# FOX_HTOL_test_2_0.net
KiCad netlist of a schematic drawn in EasyEDA Pro
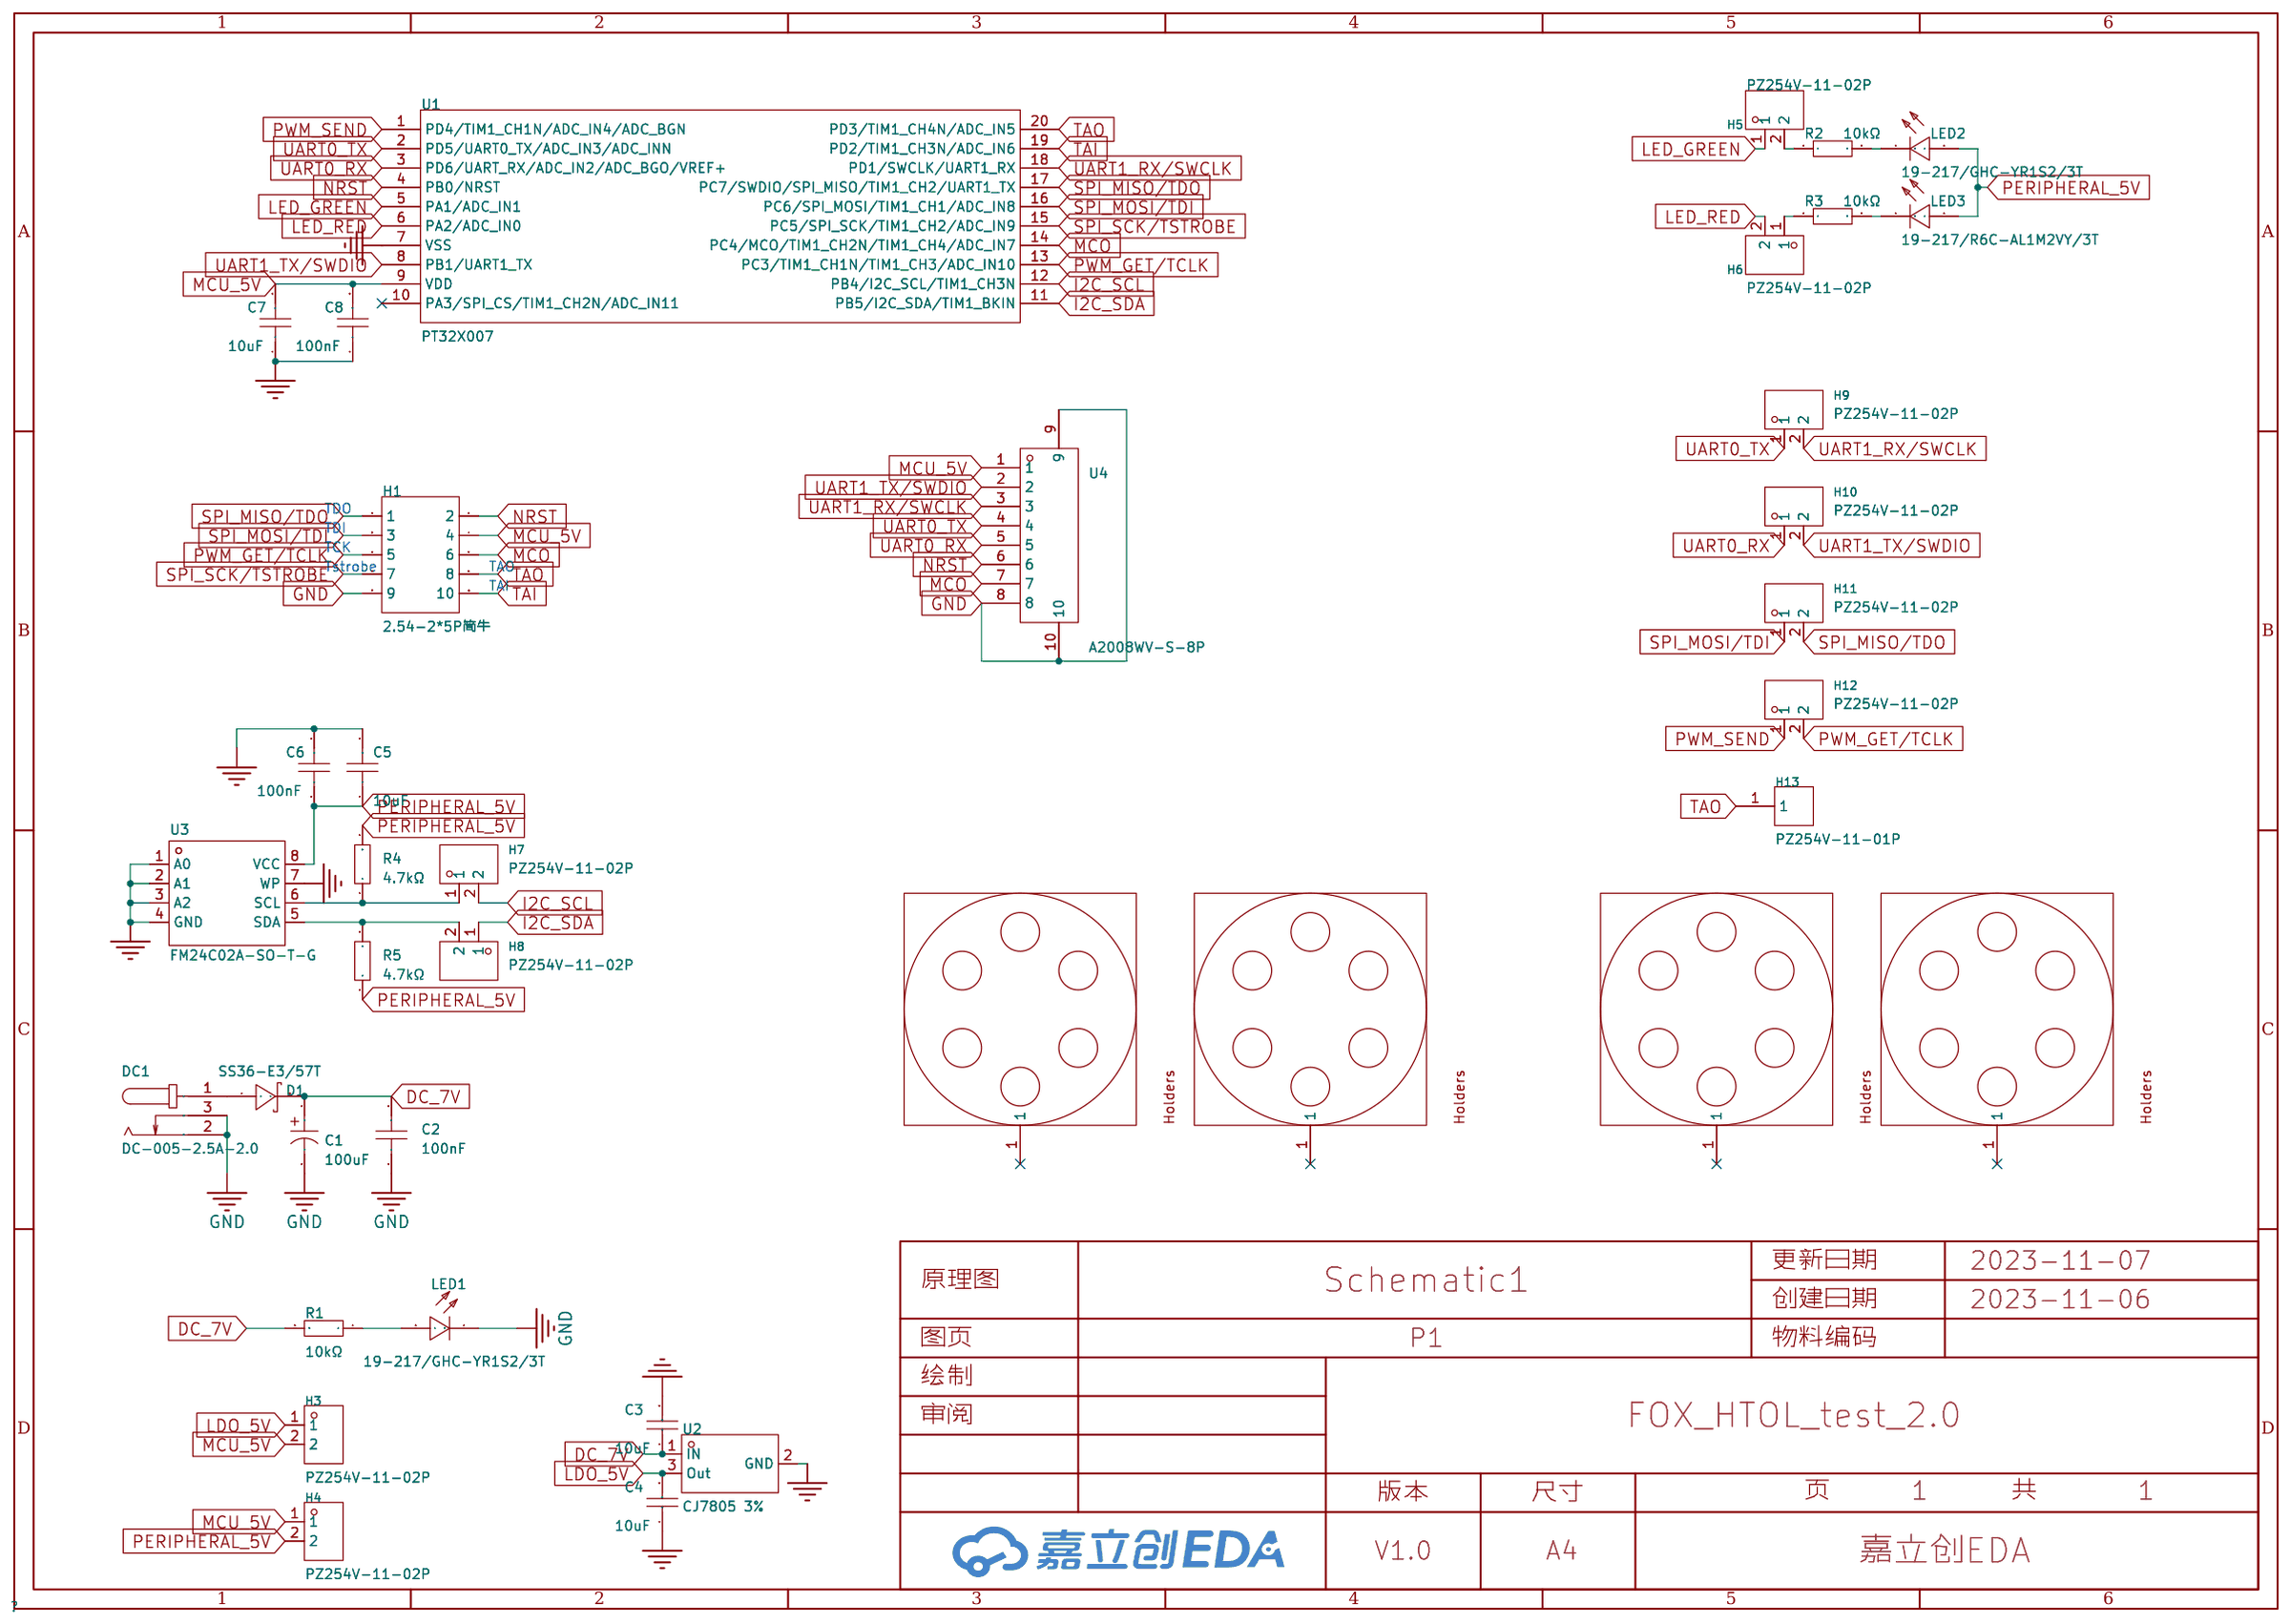
[diagram p0: schematic sheet]

(export (version "E")
  (design (tool "Eeschema 10.0.6"))
  (components
    (comp (ref "C1")
      (value "100uF")
      (footprint "easyedapro:CAP-SMD_BD6.3-L6.6-W6.6-LS7.6-FD-1")
      (description "容值:100uF;额定电压:35V;电容体直径:-;电容体长度:-;纹波电流:-;等效串联电阻:-;工作寿命:-;")
      (fields
        (field (name "Manufacturer Part") "RVE100UF35V67RV0072")
        (field (name "Manufacturer") "KNSCHA(科尼盛)")
      )
      (libsource (lib "easyedapro") (part "RVE100UF35V67RV0072"))
    )
    (comp (ref "C2")
      (value "100nF")
      (footprint "easyedapro:C0603")
      (description "容值:100nF;精度:±10%;额定电压:50V;材质(温度系数):X7R;")
      (fields
        (field (name "Manufacturer Part") "CL10B104KB8NNNC")
        (field (name "Manufacturer") "SAMSUNG(三星)")
      )
      (libsource (lib "easyedapro") (part "CL10B104KB8NNNC"))
    )
    (comp (ref "C3")
      (value "10uF")
      (footprint "easyedapro:C1206")
      (description "容值:10uF;精度:±10%;额定电压:50V;材质(温度系数):X5R;")
      (fields
        (field (name "Manufacturer Part") "CL31A106KBHNNNE")
        (field (name "Manufacturer") "SAMSUNG(三星)")
      )
      (libsource (lib "easyedapro") (part "CL31A106KBHNNNE"))
    )
    (comp (ref "C4")
      (value "10uF")
      (footprint "easyedapro:C1206")
      (description "容值:10uF;精度:±10%;额定电压:50V;材质(温度系数):X5R;")
      (fields
        (field (name "Manufacturer Part") "CL31A106KBHNNNE")
        (field (name "Manufacturer") "SAMSUNG(三星)")
      )
      (libsource (lib "easyedapro") (part "CL31A106KBHNNNE"))
    )
    (comp (ref "C5")
      (value "10uF")
      (footprint "easyedapro:C0603")
      (description "容值:10uF;精度:±20%;额定电压:25V;材质(温度系数):X5R;")
      (fields
        (field (name "Manufacturer Part") "CL10A106MA8NRNC")
        (field (name "Manufacturer") "SAMSUNG(三星)")
      )
      (libsource (lib "easyedapro") (part "CL10A106MA8NRNC"))
    )
    (comp (ref "C6")
      (value "100nF")
      (footprint "easyedapro:C0603")
      (description "容值:100nF;精度:±10%;额定电压:50V;材质(温度系数):X7R;")
      (fields
        (field (name "Manufacturer Part") "CC0603KRX7R9BB104")
        (field (name "Manufacturer") "YAGEO(国巨)")
      )
      (libsource (lib "easyedapro") (part "CC0603KRX7R9BB104"))
    )
    (comp (ref "C7")
      (value "10uF")
      (footprint "easyedapro:C0603")
      (description "容值:10uF;精度:±20%;额定电压:25V;材质(温度系数):X5R;")
      (fields
        (field (name "Manufacturer Part") "CL10A106MA8NRNC")
        (field (name "Manufacturer") "SAMSUNG(三星)")
      )
      (libsource (lib "easyedapro") (part "CL10A106MA8NRNC"))
    )
    (comp (ref "C8")
      (value "100nF")
      (footprint "easyedapro:C0603")
      (description "容值:100nF;精度:±10%;额定电压:50V;材质(温度系数):X7R;")
      (fields
        (field (name "Manufacturer Part") "CC0603KRX7R9BB104")
        (field (name "Manufacturer") "YAGEO(国巨)")
      )
      (libsource (lib "easyedapro") (part "CC0603KRX7R9BB104"))
    )
    (comp (ref "D1")
      (value "SS36-E3/57T")
      (footprint "easyedapro:SMC_L7.1-W6.2-LS8.1-R-RD")
      (description "直流反向耐压（Vr）:60V;平均整流电流（Io）:3A;正向压降（Vf）:750mV @ 3A;")
      (fields (field (name "Manufacturer") "VISHAY(威世)"))
      (libsource (lib "easyedapro") (part "SS36-E3/57T"))
    )
    (comp (ref "DC1")
      (value "DC-005-2.5A-2.0")
      (footprint "easyedapro:CONN-TH_DC-005-2.5A-2.0")
      (fields (field (name "Manufacturer") "XKB Connectivity(中国星坤)"))
      (libsource (lib "easyedapro") (part "DC-005-2.5A-2.0"))
    )
    (comp (ref "H1")
      (value "2.54-2*5P简牛")
      (footprint "easyedapro:IDC-TH_10P-P2.54_C5665")
      (description "连接器类型:简牛座;每排PIN数:5;排数:2;间距:2.54mm;行距:2.54mm;封装形式:直插;触头材质:-;触头镀层:-;")
      (fields (field (name "Manufacturer") "BOOMELE(博穆精密)"))
      (libsource (lib "easyedapro") (part "HDR-IDC-2.54-2X5P"))
    )
    (comp (ref "H3")
      (value "PZ254V-11-02P")
      (footprint "easyedapro:HDR-TH_2P-P2.54-V-M")
      (fields (field (name "Manufacturer") "XFCN(兴飞)"))
      (libsource (lib "easyedapro") (part "PZ254V-11-02P"))
    )
    (comp (ref "H4")
      (value "PZ254V-11-02P")
      (footprint "easyedapro:HDR-TH_2P-P2.54-V-M")
      (fields (field (name "Manufacturer") "XFCN(兴飞)"))
      (libsource (lib "easyedapro") (part "PZ254V-11-02P"))
    )
    (comp (ref "H5")
      (value "PZ254V-11-02P")
      (footprint "easyedapro:HDR-TH_2P-P2.54-V-M")
      (fields (field (name "Manufacturer") "XFCN(兴飞)"))
      (libsource (lib "easyedapro") (part "PZ254V-11-02P"))
    )
    (comp (ref "H6")
      (value "PZ254V-11-02P")
      (footprint "easyedapro:HDR-TH_2P-P2.54-V-M")
      (fields (field (name "Manufacturer") "XFCN(兴飞)"))
      (libsource (lib "easyedapro") (part "PZ254V-11-02P"))
    )
    (comp (ref "H7")
      (value "PZ254V-11-02P")
      (footprint "easyedapro:HDR-TH_2P-P2.54-V-M")
      (fields (field (name "Manufacturer") "XFCN(兴飞)"))
      (libsource (lib "easyedapro") (part "PZ254V-11-02P"))
    )
    (comp (ref "H8")
      (value "PZ254V-11-02P")
      (footprint "easyedapro:HDR-TH_2P-P2.54-V-M")
      (fields (field (name "Manufacturer") "XFCN(兴飞)"))
      (libsource (lib "easyedapro") (part "PZ254V-11-02P"))
    )
    (comp (ref "H9")
      (value "PZ254V-11-02P")
      (footprint "easyedapro:HDR-TH_2P-P2.54-V-M")
      (fields (field (name "Manufacturer") "XFCN(兴飞)"))
      (libsource (lib "easyedapro") (part "PZ254V-11-02P"))
    )
    (comp (ref "H10")
      (value "PZ254V-11-02P")
      (footprint "easyedapro:HDR-TH_2P-P2.54-V-M")
      (fields (field (name "Manufacturer") "XFCN(兴飞)"))
      (libsource (lib "easyedapro") (part "PZ254V-11-02P"))
    )
    (comp (ref "H11")
      (value "PZ254V-11-02P")
      (footprint "easyedapro:HDR-TH_2P-P2.54-V-M")
      (fields (field (name "Manufacturer") "XFCN(兴飞)"))
      (libsource (lib "easyedapro") (part "PZ254V-11-02P"))
    )
    (comp (ref "H12")
      (value "PZ254V-11-02P")
      (footprint "easyedapro:HDR-TH_2P-P2.54-V-M")
      (fields (field (name "Manufacturer") "XFCN(兴飞)"))
      (libsource (lib "easyedapro") (part "PZ254V-11-02P"))
    )
    (comp (ref "H13")
      (value "PZ254V-11-01P")
      (footprint "easyedapro:HDR-TH_1P-P2.54-V-M")
      (fields (field (name "Manufacturer") "XFCN(兴飞)"))
      (libsource (lib "easyedapro") (part "PZ254V-11-01P"))
    )
    (comp (ref "J2")
      (value "~")
      (footprint "easyedapro:DEMO板安装孔")
      (libsource (lib "easyedapro") (part "螺孔_3.1X6MM"))
    )
    (comp (ref "J3")
      (value "~")
      (footprint "easyedapro:DEMO板安装孔")
      (libsource (lib "easyedapro") (part "螺孔_3.1X6MM"))
    )
    (comp (ref "J4")
      (value "~")
      (footprint "easyedapro:DEMO板安装孔")
      (libsource (lib "easyedapro") (part "螺孔_3.1X6MM"))
    )
    (comp (ref "J5")
      (value "~")
      (footprint "easyedapro:DEMO板安装孔")
      (libsource (lib "easyedapro") (part "螺孔_3.1X6MM"))
    )
    (comp (ref "LED1")
      (value "19-217/GHC-YR1S2/3T")
      (footprint "easyedapro:LED0603-RD")
      (fields (field (name "Manufacturer") "EVERLIGHT(亿光)"))
      (libsource (lib "easyedapro") (part "19-217/GHC-YR1S2/3T"))
    )
    (comp (ref "LED2")
      (value "19-217/GHC-YR1S2/3T")
      (footprint "easyedapro:LED0603-RD")
      (fields (field (name "Manufacturer") "EVERLIGHT(亿光)"))
      (libsource (lib "easyedapro") (part "19-217/GHC-YR1S2/3T"))
    )
    (comp (ref "LED3")
      (value "19-217/R6C-AL1M2VY/3T")
      (footprint "easyedapro:LED0603-RD")
      (description "发光颜色:红灯;二极管配置:-;透镜颜色:无色透明;主波长:617.5nm;色温:-;功率:60mW;发光角度:120°;安装方式:-;工作温度:-40°C~+85°C;")
      (fields (field (name "Manufacturer") "EVERLIGHT(亿光)"))
      (libsource (lib "easyedapro") (part "19-217/R6C-AL1M2VY/3T"))
    )
    (comp (ref "R1")
      (value "10kΩ")
      (footprint "easyedapro:R0603")
      (description "电阻类型:厚膜电阻;阻值:10kΩ;精度:±1%;功率:100mW;温度系数:±100ppm/℃;最大工作电压:75V;工作温度范围:-55℃~+155℃;")
      (fields
        (field (name "Manufacturer Part") "0603WAF1002T5E")
        (field (name "Manufacturer") "UNI-ROYAL(厚声)")
      )
      (libsource (lib "easyedapro") (part "0603WAF1002T5E"))
    )
    (comp (ref "R2")
      (value "10kΩ")
      (footprint "easyedapro:R0603")
      (description "电阻类型:厚膜电阻;阻值:10kΩ;精度:±1%;功率:100mW;")
      (fields
        (field (name "Manufacturer Part") "0603WAF1002T5E")
        (field (name "Manufacturer") "UNI-ROYAL(厚声)")
      )
      (libsource (lib "easyedapro") (part "0603WAF1002T5E"))
    )
    (comp (ref "R3")
      (value "10kΩ")
      (footprint "easyedapro:R0603")
      (description "电阻类型:厚膜电阻;阻值:10kΩ;精度:±1%;功率:100mW;")
      (fields
        (field (name "Manufacturer Part") "0603WAF1002T5E")
        (field (name "Manufacturer") "UNI-ROYAL(厚声)")
      )
      (libsource (lib "easyedapro") (part "0603WAF1002T5E"))
    )
    (comp (ref "R4")
      (value "4.7kΩ")
      (footprint "easyedapro:R0603")
      (description "电阻类型:厚膜电阻;阻值:4.7kΩ;精度:±1%;功率:100mW;温度系数:±100ppm/°C;")
      (fields
        (field (name "Manufacturer Part") "0603WAF4701T5E")
        (field (name "Manufacturer") "UNI-ROYAL(厚声)")
      )
      (libsource (lib "easyedapro") (part "0603WAF4701T5E"))
    )
    (comp (ref "R5")
      (value "4.7kΩ")
      (footprint "easyedapro:R0603")
      (description "电阻类型:厚膜电阻;阻值:4.7kΩ;精度:±1%;功率:100mW;温度系数:±100ppm/°C;")
      (fields
        (field (name "Manufacturer Part") "0603WAF4701T5E")
        (field (name "Manufacturer") "UNI-ROYAL(厚声)")
      )
      (libsource (lib "easyedapro") (part "0603WAF4701T5E"))
    )
    (comp (ref "U1")
      (value "PT32X007")
      (footprint "easyedapro:TSSOP-20_L6.5-W4.4-P0.65-LS6.4-BL")
      (libsource (lib "easyedapro") (part "PT32X007"))
    )
    (comp (ref "U2")
      (value "CJ7805 3%")
      (footprint "easyedapro:TO-252-2_L6.6-W6.1-P4.58-LS10.1-BR-CW")
      (description "输出类型:固定;输出极性:正;最大输入电压:35V;输出电压:5V;输出电流:1.5A;")
      (fields (field (name "Manufacturer") "CJ(江苏长电/长晶)"))
      (libsource (lib "easyedapro") (part "CJ7805 3%"))
    )
    (comp (ref "U3")
      (value "FM24C02A-SO-T-G")
      (footprint "easyedapro:SOP-8_L5.0-W4.0-P1.27-LS6.2-BL")
      (description "2-Kbit(256 x 8bit)，I2C接口，工作电压：1.7V to 5.5V")
      (fields (field (name "Manufacturer") "FM(复旦微)"))
      (libsource (lib "easyedapro") (part "FM24C02A-SO-TR"))
    )
    (comp (ref "U4")
      (value "A2008WV-S-8P")
      (footprint "easyedapro:CONN-SMD_A2008WV-S-8P")
      (description "参考系列:PH;间距:2mm;插针结构:1x8P;排数:1;每排PIN数:8;行距:-;安装方式:-;触头材质:黄铜;")
      (fields (field (name "Manufacturer") "CJT(长江连接器)"))
      (libsource (lib "easyedapro") (part "A2008WV-S-8P"))
    )
  )
  (nets
    (net (code "1") (name "DC_7V") (class "Default")
      (node (ref "C1") (pin "1") (pinfunction "1_1") (pintype "input"))
      (node (ref "C2") (pin "2") (pinfunction "2_2") (pintype "input"))
      (node (ref "C3") (pin "1") (pinfunction "1_1") (pintype "input"))
      (node (ref "D1") (pin "2") (pinfunction "K_2") (pintype "input"))
      (node (ref "R1") (pin "2") (pinfunction "2_2") (pintype "input"))
      (node (ref "U2") (pin "1") (pinfunction "IN_1") (pintype "input"))
    )
    (net (code "2") (name "GND") (class "Default")
      (node (ref "C1") (pin "2") (pinfunction "2_2") (pintype "input"))
      (node (ref "C2") (pin "1") (pinfunction "1_1") (pintype "input"))
      (node (ref "C3") (pin "2") (pinfunction "2_2") (pintype "input"))
      (node (ref "C4") (pin "1") (pinfunction "1_1") (pintype "input"))
      (node (ref "C5") (pin "2") (pinfunction "2_2") (pintype "input"))
      (node (ref "C6") (pin "2") (pinfunction "2_2") (pintype "input"))
      (node (ref "C7") (pin "1") (pinfunction "1_1") (pintype "input"))
      (node (ref "C8") (pin "1") (pinfunction "1_1") (pintype "input"))
      (node (ref "DC1") (pin "2") (pinfunction "2_2") (pintype "input"))
      (node (ref "DC1") (pin "3") (pinfunction "3_3") (pintype "input"))
      (node (ref "H1") (pin "9") (pinfunction "9_9") (pintype "input"))
      (node (ref "LED1") (pin "1") (pinfunction "C_1") (pintype "input"))
      (node (ref "U1") (pin "7") (pinfunction "VSS_7") (pintype "input"))
      (node (ref "U2") (pin "2") (pinfunction "GND_2") (pintype "input"))
      (node (ref "U3") (pin "1") (pinfunction "A0_1") (pintype "unspecified"))
      (node (ref "U3") (pin "2") (pinfunction "A1_2") (pintype "unspecified"))
      (node (ref "U3") (pin "3") (pinfunction "A2_3") (pintype "unspecified"))
      (node (ref "U3") (pin "4") (pinfunction "GND_4") (pintype "unspecified"))
      (node (ref "U3") (pin "7") (pinfunction "WP_7") (pintype "unspecified"))
      (node (ref "U4") (pin "10") (pinfunction "10_10") (pintype "input"))
      (node (ref "U4") (pin "8") (pinfunction "8_8") (pintype "input"))
      (node (ref "U4") (pin "9") (pinfunction "9_9") (pintype "input"))
    )
    (net (code "3") (name "I2C_SCL") (class "Default")
      (node (ref "H7") (pin "2") (pinfunction "2_2") (pintype "input"))
      (node (ref "U1") (pin "12") (pinfunction "PB4/I2C_SCL/TIM1_CH3N_12") (pintype "input"))
    )
    (net (code "4") (name "I2C_SDA") (class "Default")
      (node (ref "H8") (pin "1") (pinfunction "1_1") (pintype "input"))
      (node (ref "U1") (pin "11") (pinfunction "PB5/I2C_SDA/TIM1_BKIN_11") (pintype "input"))
    )
    (net (code "5") (name "LDO_5V") (class "Default")
      (node (ref "C4") (pin "2") (pinfunction "2_2") (pintype "input"))
      (node (ref "H3") (pin "1") (pinfunction "1_1") (pintype "input"))
      (node (ref "U2") (pin "3") (pinfunction "Out_3") (pintype "input"))
    )
    (net (code "6") (name "LED_GREEN") (class "Default")
      (node (ref "H5") (pin "1") (pinfunction "1_1") (pintype "input"))
      (node (ref "U1") (pin "5") (pinfunction "PA1/ADC_IN1_5") (pintype "input"))
    )
    (net (code "7") (name "LED_RED") (class "Default")
      (node (ref "H6") (pin "2") (pinfunction "2_2") (pintype "input"))
      (node (ref "U1") (pin "6") (pinfunction "PA2/ADC_IN0_6") (pintype "input"))
    )
    (net (code "8") (name "MCO") (class "Default")
      (node (ref "H1") (pin "6") (pinfunction "6_6") (pintype "input"))
      (node (ref "U1") (pin "14") (pinfunction "PC4/MCO/TIM1_CH2N/TIM1_CH4/ADC_IN7_14") (pintype "input"))
      (node (ref "U4") (pin "7") (pinfunction "7_7") (pintype "input"))
    )
    (net (code "9") (name "MCU_5V") (class "Default")
      (node (ref "C7") (pin "2") (pinfunction "2_2") (pintype "input"))
      (node (ref "C8") (pin "2") (pinfunction "2_2") (pintype "input"))
      (node (ref "H1") (pin "4") (pinfunction "4_4") (pintype "input"))
      (node (ref "H3") (pin "2") (pinfunction "2_2") (pintype "input"))
      (node (ref "H4") (pin "1") (pinfunction "1_1") (pintype "input"))
      (node (ref "U1") (pin "9") (pinfunction "VDD_9") (pintype "input"))
      (node (ref "U4") (pin "1") (pinfunction "1_1") (pintype "input"))
    )
    (net (code "10") (name "NRST") (class "Default")
      (node (ref "H1") (pin "2") (pinfunction "2_2") (pintype "input"))
      (node (ref "U1") (pin "4") (pinfunction "PB0/NRST_4") (pintype "input"))
      (node (ref "U4") (pin "6") (pinfunction "6_6") (pintype "input"))
    )
    (net (code "11") (name "Net-(D1-A)") (class "Default")
      (node (ref "D1") (pin "1") (pinfunction "A_1") (pintype "input"))
      (node (ref "DC1") (pin "1") (pinfunction "1_1") (pintype "input"))
    )
    (net (code "12") (name "Net-(H5-Pad2)") (class "Default")
      (node (ref "H5") (pin "2") (pinfunction "2_2") (pintype "input"))
      (node (ref "R2") (pin "1") (pinfunction "1_1") (pintype "input"))
    )
    (net (code "13") (name "Net-(H6-Pad1)") (class "Default")
      (node (ref "H6") (pin "1") (pinfunction "1_1") (pintype "input"))
      (node (ref "R3") (pin "1") (pinfunction "1_1") (pintype "input"))
    )
    (net (code "14") (name "Net-(LED1-A)") (class "Default")
      (node (ref "LED1") (pin "2") (pinfunction "A_2") (pintype "input"))
      (node (ref "R1") (pin "1") (pinfunction "1_1") (pintype "input"))
    )
    (net (code "15") (name "Net-(LED2-C)") (class "Default")
      (node (ref "LED2") (pin "1") (pinfunction "C_1") (pintype "input"))
      (node (ref "R2") (pin "2") (pinfunction "2_2") (pintype "input"))
    )
    (net (code "16") (name "Net-(LED3-C)") (class "Default")
      (node (ref "LED3") (pin "1") (pinfunction "C_1") (pintype "input"))
      (node (ref "R3") (pin "2") (pinfunction "2_2") (pintype "input"))
    )
    (net (code "17") (name "Net-(U3-SCL)") (class "Default")
      (node (ref "H7") (pin "1") (pinfunction "1_1") (pintype "input"))
      (node (ref "R4") (pin "1") (pinfunction "1_1") (pintype "input"))
      (node (ref "U3") (pin "6") (pinfunction "SCL_6") (pintype "unspecified"))
    )
    (net (code "18") (name "Net-(U3-SDA)") (class "Default")
      (node (ref "H8") (pin "2") (pinfunction "2_2") (pintype "input"))
      (node (ref "R5") (pin "2") (pinfunction "2_2") (pintype "input"))
      (node (ref "U3") (pin "5") (pinfunction "SDA_5") (pintype "unspecified"))
    )
    (net (code "19") (name "PERIPHERAL_5V") (class "Default")
      (node (ref "C5") (pin "1") (pinfunction "1_1") (pintype "input"))
      (node (ref "C6") (pin "1") (pinfunction "1_1") (pintype "input"))
      (node (ref "H4") (pin "2") (pinfunction "2_2") (pintype "input"))
      (node (ref "LED2") (pin "2") (pinfunction "A_2") (pintype "input"))
      (node (ref "LED3") (pin "2") (pinfunction "A_2") (pintype "input"))
      (node (ref "R4") (pin "2") (pinfunction "2_2") (pintype "input"))
      (node (ref "R5") (pin "1") (pinfunction "1_1") (pintype "input"))
      (node (ref "U3") (pin "8") (pinfunction "VCC_8") (pintype "unspecified"))
    )
    (net (code "20") (name "PWM_GET{slash}TCLK") (class "Default")
      (node (ref "H1") (pin "5") (pinfunction "5_5") (pintype "input"))
      (node (ref "H12") (pin "2") (pinfunction "2_2") (pintype "input"))
      (node (ref "U1") (pin "13") (pinfunction "PC3/TIM1_CH1N/TIM1_CH3/ADC_IN10_13") (pintype "input"))
    )
    (net (code "21") (name "PWM_SEND") (class "Default")
      (node (ref "H12") (pin "1") (pinfunction "1_1") (pintype "input"))
      (node (ref "U1") (pin "1") (pinfunction "PD4/TIM1_CH1N/ADC_IN4/ADC_BGN_1") (pintype "input"))
    )
    (net (code "22") (name "SPI_MISO{slash}TDO") (class "Default")
      (node (ref "H1") (pin "1") (pinfunction "1_1") (pintype "input"))
      (node (ref "H11") (pin "2") (pinfunction "2_2") (pintype "input"))
      (node (ref "U1") (pin "17") (pinfunction "PC7/SWDIO/SPI_MISO/TIM1_CH2/UART1_TX_17") (pintype "input"))
    )
    (net (code "23") (name "SPI_MOSI{slash}TDI") (class "Default")
      (node (ref "H1") (pin "3") (pinfunction "3_3") (pintype "input"))
      (node (ref "H11") (pin "1") (pinfunction "1_1") (pintype "input"))
      (node (ref "U1") (pin "16") (pinfunction "PC6/SPI_MOSI/TIM1_CH1/ADC_IN8_16") (pintype "input"))
    )
    (net (code "24") (name "SPI_SCK{slash}TSTROBE") (class "Default")
      (node (ref "H1") (pin "7") (pinfunction "7_7") (pintype "input"))
      (node (ref "U1") (pin "15") (pinfunction "PC5/SPI_SCK/TIM1_CH2/ADC_IN9_15") (pintype "input"))
    )
    (net (code "25") (name "TAI") (class "Default")
      (node (ref "H1") (pin "10") (pinfunction "10_10") (pintype "input"))
      (node (ref "U1") (pin "19") (pinfunction "PD2/TIM1_CH3N/ADC_IN6_19") (pintype "input"))
    )
    (net (code "26") (name "TAO") (class "Default")
      (node (ref "H1") (pin "8") (pinfunction "8_8") (pintype "input"))
      (node (ref "H13") (pin "1") (pinfunction "1_1") (pintype "input"))
      (node (ref "U1") (pin "20") (pinfunction "PD3/TIM1_CH4N/ADC_IN5_20") (pintype "input"))
    )
    (net (code "27") (name "UART0_RX") (class "Default")
      (node (ref "H10") (pin "1") (pinfunction "1_1") (pintype "input"))
      (node (ref "U1") (pin "3") (pinfunction "PD6/UART_RX/ADC_IN2/ADC_BGO/VREF+_3") (pintype "input"))
      (node (ref "U4") (pin "5") (pinfunction "5_5") (pintype "input"))
    )
    (net (code "28") (name "UART0_TX") (class "Default")
      (node (ref "H9") (pin "1") (pinfunction "1_1") (pintype "input"))
      (node (ref "U1") (pin "2") (pinfunction "PD5/UART0_TX/ADC_IN3/ADC_INN_2") (pintype "input"))
      (node (ref "U4") (pin "4") (pinfunction "4_4") (pintype "input"))
    )
    (net (code "29") (name "UART1_RX{slash}SWCLK") (class "Default")
      (node (ref "H9") (pin "2") (pinfunction "2_2") (pintype "input"))
      (node (ref "U1") (pin "18") (pinfunction "PD1/SWCLK/UART1_RX_18") (pintype "input"))
      (node (ref "U4") (pin "3") (pinfunction "3_3") (pintype "input"))
    )
    (net (code "30") (name "UART1_TX{slash}SWDIO") (class "Default")
      (node (ref "H10") (pin "2") (pinfunction "2_2") (pintype "input"))
      (node (ref "U1") (pin "8") (pinfunction "PB1/UART1_TX_8") (pintype "input"))
      (node (ref "U4") (pin "2") (pinfunction "2_2") (pintype "input"))
    )
    (net (code "31") (name "unconnected-(J2-Pad1)") (class "Default")
      (node (ref "J2") (pin "1") (pinfunction "1_1") (pintype "input+no_connect"))
    )
    (net (code "32") (name "unconnected-(J3-Pad1)") (class "Default")
      (node (ref "J3") (pin "1") (pinfunction "1_1") (pintype "input+no_connect"))
    )
    (net (code "33") (name "unconnected-(J4-Pad1)") (class "Default")
      (node (ref "J4") (pin "1") (pinfunction "1_1") (pintype "input+no_connect"))
    )
    (net (code "34") (name "unconnected-(J5-Pad1)") (class "Default")
      (node (ref "J5") (pin "1") (pinfunction "1_1") (pintype "input+no_connect"))
    )
    (net (code "35") (name "unconnected-(U1-PA3{slash}SPI_CS{slash}TIM1_CH2N{slash}ADC_IN11-Pad10)") (class "Default")
      (node (ref "U1") (pin "10") (pinfunction "PA3/SPI_CS/TIM1_CH2N/ADC_IN11_10") (pintype "input+no_connect"))
    )
  )
)
